# P1.net
KiCad netlist of a schematic drawn in Altium Designer
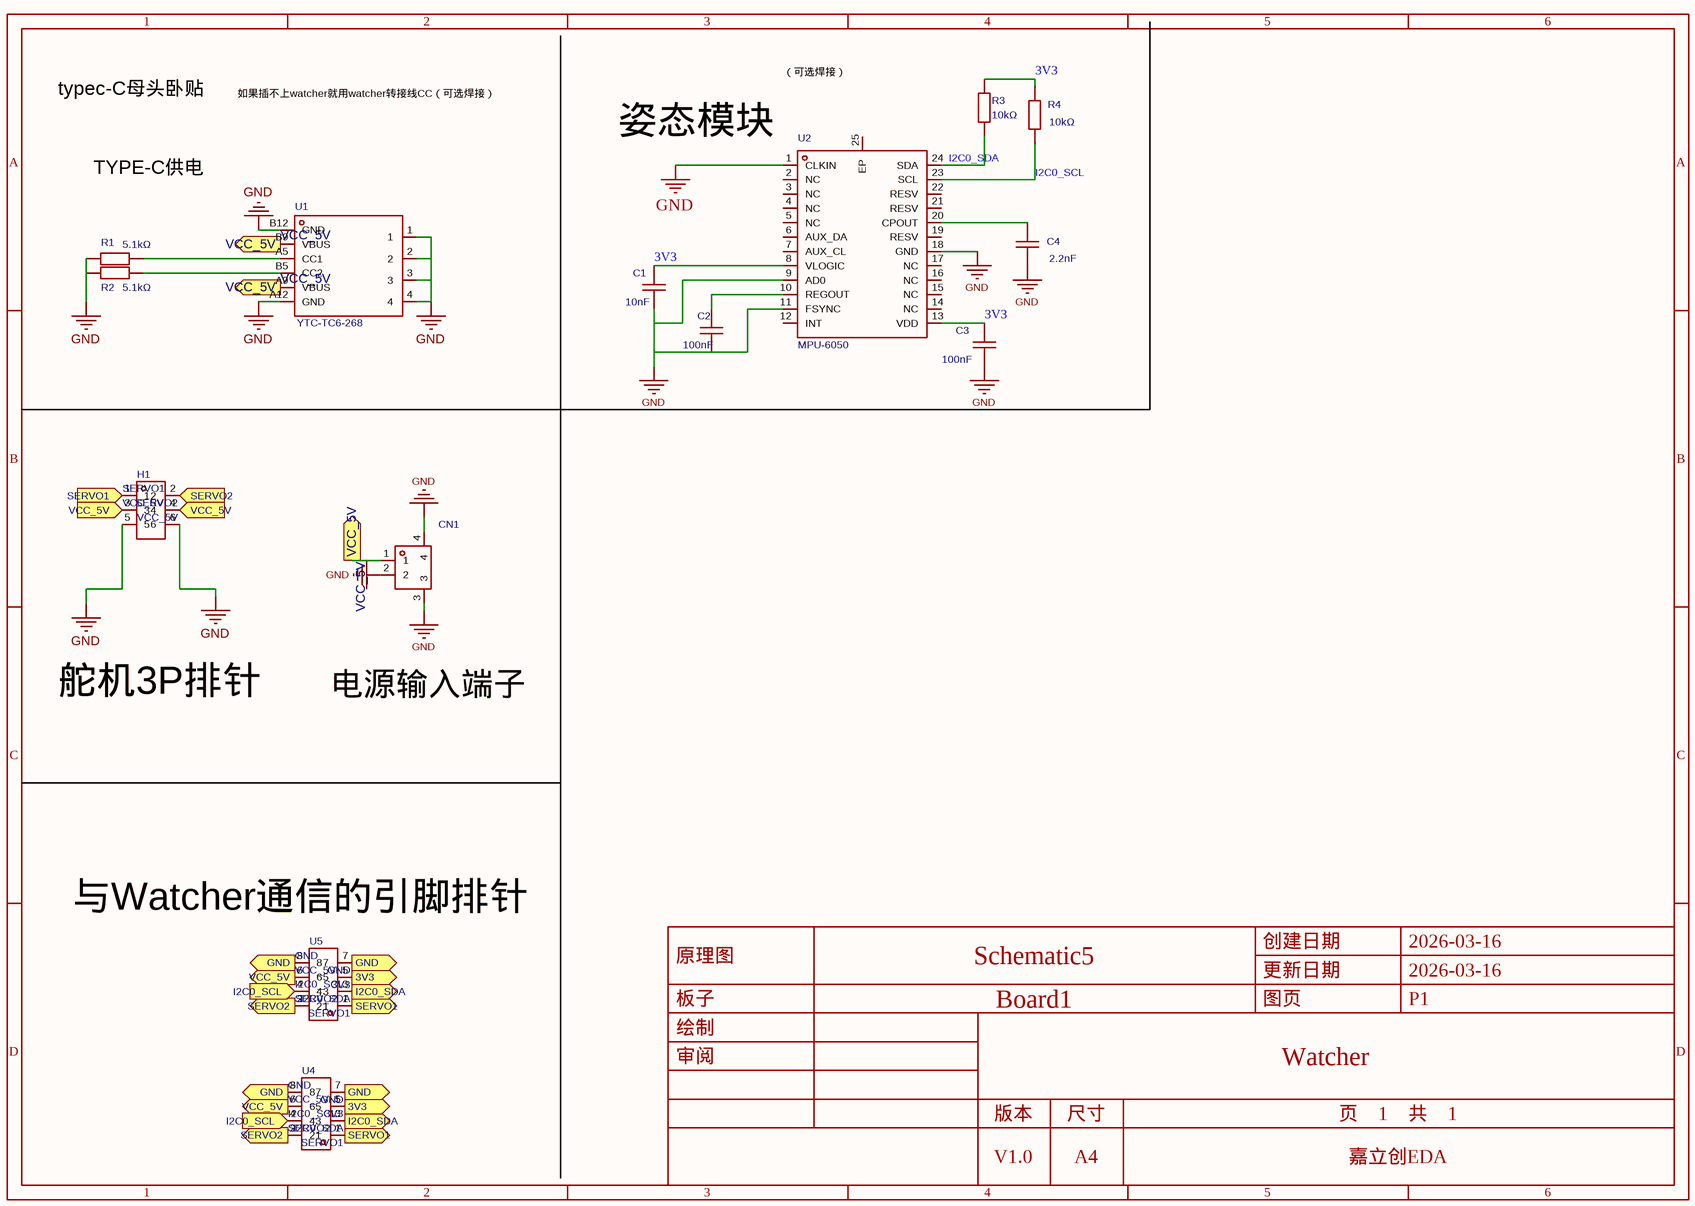
[diagram p0: P1.schdoc]

(export (version "E")
  (design (tool "Eeschema 10.0.6"))
  (components
    (comp (ref "C1")
      (value "10nF")
      (footprint "C0603")
      (description "容值:10nF;精度:±10%;额定电压:50V;材质(温度系数):X7R;")
      (fields (field (name "TOLERANCE") "±10%") (field (name "MANUFACTURER") "YAGEO(国巨)"))
      (libsource (lib "altium-import") (part "root_1_CC0603KRX7R9BB103_"))
    )
    (comp (ref "C2")
      (value "100nF")
      (footprint "C0603")
      (description "容值:100nF;精度:±10%;额定电压:50V;材质(温度系数):X7R;")
      (fields (field (name "TOLERANCE") "±10%") (field (name "MANUFACTURER") "FH(风华)"))
      (libsource (lib "altium-import") (part "root_1_0603B104K500NT_"))
    )
    (comp (ref "C3")
      (value "100nF")
      (footprint "C0603")
      (description "容值:100nF;精度:±10%;额定电压:50V;材质(温度系数):X7R;")
      (fields (field (name "TOLERANCE") "±10%") (field (name "MANUFACTURER") "FH(风华)"))
      (libsource (lib "altium-import") (part "root_1_0603B104K500NT_"))
    )
    (comp (ref "C4")
      (value "2.2nF")
      (footprint "C0603")
      (description "容值:2.2nF;精度:±10%;额定电压:50V;材质(温度系数):X7R;")
      (fields (field (name "MANUFACTURER") "FH(风华)") (field (name "MANUFACTURER PART") "0603B222K500NT"))
      (libsource (lib "altium-import") (part "root_1_0603B222K500NT_"))
    )
    (comp (ref "CN1")
      (value "SH1.0mm立式")
      (footprint "CONN-SMD_2P-P1.00_HC-1.0-2PLT")
      (libsource (lib "altium-import") (part "root_0_SH1.0mm立式_"))
    )
    (comp (ref "H1")
      (value "PZ254V-12-6P")
      (footprint "HDR-TH_6P-P2.54-V-M-R2-C3-S2.54")
      (fields (field (name "MANUFACTURER") "XFCN(兴飞)"))
      (libsource (lib "altium-import") (part "root_0_PZ254V-12-6P_"))
    )
    (comp (ref "R1")
      (value "5.1kΩ")
      (footprint "R0603_1")
      (description "电阻类型:厚膜电阻;阻值:5.1kΩ;精度:±1%;功率:100mW;温度系数:±100ppm/;最大工作电压:75V;工作温度范围:-55~+155;")
      (fields
        (field (name "MANUFACTURER") "UNI-ROYAL(厚声)")
        (field (name "MANUFACTURER PART") "0603WAF5101T5E")
      )
      (libsource (lib "altium-import") (part "root_0_0603WAF5101T5E_"))
    )
    (comp (ref "R2")
      (value "5.1kΩ")
      (footprint "R0603_1")
      (description "电阻类型:厚膜电阻;阻值:5.1kΩ;精度:±1%;功率:100mW;温度系数:±100ppm/;最大工作电压:75V;工作温度范围:-55~+155;")
      (fields
        (field (name "MANUFACTURER") "UNI-ROYAL(厚声)")
        (field (name "MANUFACTURER PART") "0603WAF5101T5E")
      )
      (libsource (lib "altium-import") (part "root_0_0603WAF5101T5E_"))
    )
    (comp (ref "R3")
      (value "10kΩ")
      (footprint "R0603")
      (description "电阻类型:厚膜电阻;阻值:10kΩ;精度:±1%;功率:100mW;最大工作电压:75V;温度系数:±100ppm/℃;")
      (fields (field (name "MANUFACTURER") "YAGEO(国巨)") (field (name "MANUFACTURER PART") "RC0603FR-0710KL"))
      (libsource (lib "altium-import") (part "root_1_RC0603FR-0710KL_"))
    )
    (comp (ref "R4")
      (value "10kΩ")
      (footprint "R0603")
      (description "电阻类型:厚膜电阻;阻值:10kΩ;精度:±1%;功率:100mW;最大工作电压:75V;温度系数:±100ppm/℃;")
      (fields (field (name "MANUFACTURER") "YAGEO(国巨)") (field (name "MANUFACTURER PART") "RC0603FR-0710KL"))
      (libsource (lib "altium-import") (part "root_1_RC0603FR-0710KL_"))
    )
    (comp (ref "U1")
      (value "YTC-TC6-268")
      (footprint "TYPE-C-SMD_YIYUAN_YTC-TC6-268")
      (description "连接器类型:Type-C;公母:母座;触点数量:6;")
      (fields (field (name "MANUFACTURER") "YIYUAN(怡远)"))
      (libsource (lib "altium-import") (part "root_0_YTC-TC6-268_"))
    )
    (comp (ref "U2")
      (value "MPU-6050")
      (footprint "QFN-24_L4.0-W4.0-P0.50-BL-EP2.7")
      (description "传感器类型:加速度计陀螺仪;")
      (fields (field (name "MANUFACTURER") "TDK InvenSense(应美盛)"))
      (libsource (lib "altium-import") (part "root_0_MPU-6050_"))
    )
    (comp (ref "U4")
      (value "PZ2.54-2*4")
      (footprint "HDR-TH_8P-P2.54-V-M-R2-C4-S2.54")
      (fields (field (name "MANUFACTURER") "ZHOURI(洲日)"))
      (libsource (lib "altium-import") (part "root_2_PZ2.54-2*4_"))
    )
    (comp (ref "U5")
      (value "PZ2.54-2*4")
      (footprint "HDR-TH_8P-P2.54-V-M-R2-C4-S2.54")
      (fields (field (name "MANUFACTURER") "ZHOURI(洲日)"))
      (libsource (lib "altium-import") (part "root_2_PZ2.54-2*4_"))
    )
  )
  (nets
    (net (code "1") (name "/3V3") (class "Default")
      (node (ref "C1") (pin "2") (pinfunction "2_2") (pintype "passive"))
      (node (ref "C3") (pin "2") (pinfunction "2_2") (pintype "passive"))
      (node (ref "R3") (pin "2") (pinfunction "2_2") (pintype "passive"))
      (node (ref "R4") (pin "2") (pinfunction "2_2") (pintype "passive"))
      (node (ref "U2") (pin "13") (pinfunction "VDD_13") (pintype "passive"))
      (node (ref "U2") (pin "8") (pinfunction "VLOGIC_8") (pintype "passive"))
      (node (ref "U4") (pin "5") (pinfunction "5_5") (pintype "passive"))
      (node (ref "U5") (pin "5") (pinfunction "5_5") (pintype "passive"))
    )
    (net (code "2") (name "/I2C0_SCL") (class "Default")
      (node (ref "R4") (pin "1") (pinfunction "1_1") (pintype "passive"))
      (node (ref "U2") (pin "23") (pinfunction "SCL_23") (pintype "passive"))
      (node (ref "U4") (pin "4") (pinfunction "4_4") (pintype "passive"))
      (node (ref "U5") (pin "4") (pinfunction "4_4") (pintype "passive"))
    )
    (net (code "3") (name "/I2C0_SDA") (class "Default")
      (node (ref "R3") (pin "1") (pinfunction "1_1") (pintype "passive"))
      (node (ref "U2") (pin "24") (pinfunction "SDA_24") (pintype "passive"))
      (node (ref "U4") (pin "3") (pinfunction "3_3") (pintype "passive"))
      (node (ref "U5") (pin "3") (pinfunction "3_3") (pintype "passive"))
    )
    (net (code "4") (name "/SERVO1") (class "Default")
      (node (ref "H1") (pin "1") (pinfunction "1_1") (pintype "passive"))
      (node (ref "U4") (pin "1") (pinfunction "1_1") (pintype "passive"))
      (node (ref "U5") (pin "1") (pinfunction "1_1") (pintype "passive"))
    )
    (net (code "5") (name "/SERVO2") (class "Default")
      (node (ref "H1") (pin "2") (pinfunction "2_2") (pintype "passive"))
      (node (ref "U4") (pin "2") (pinfunction "2_2") (pintype "passive"))
      (node (ref "U5") (pin "2") (pinfunction "2_2") (pintype "passive"))
    )
    (net (code "6") (name "/VCC_5V") (class "Default")
      (node (ref "CN1") (pin "1") (pinfunction "1_1") (pintype "passive"))
      (node (ref "H1") (pin "3") (pinfunction "3_3") (pintype "passive"))
      (node (ref "H1") (pin "4") (pinfunction "4_4") (pintype "passive"))
      (node (ref "U1") (pin "A9") (pinfunction "VBUS_A9") (pintype "passive"))
      (node (ref "U1") (pin "B9") (pinfunction "VBUS_B9") (pintype "passive"))
      (node (ref "U4") (pin "6") (pinfunction "6_6") (pintype "passive"))
      (node (ref "U5") (pin "6") (pinfunction "6_6") (pintype "passive"))
    )
    (net (code "7") (name "GND") (class "Default")
      (node (ref "C1") (pin "1") (pinfunction "1_1") (pintype "passive"))
      (node (ref "C2") (pin "1") (pinfunction "1_1") (pintype "passive"))
      (node (ref "C3") (pin "1") (pinfunction "1_1") (pintype "passive"))
      (node (ref "C4") (pin "1") (pinfunction "1_1") (pintype "passive"))
      (node (ref "CN1") (pin "2") (pinfunction "2_2") (pintype "passive"))
      (node (ref "CN1") (pin "3") (pinfunction "3_3") (pintype "passive"))
      (node (ref "CN1") (pin "4") (pinfunction "4_4") (pintype "passive"))
      (node (ref "H1") (pin "5") (pinfunction "5_5") (pintype "passive"))
      (node (ref "H1") (pin "6") (pinfunction "6_6") (pintype "passive"))
      (node (ref "R1") (pin "1") (pinfunction "1_1") (pintype "passive"))
      (node (ref "R2") (pin "1") (pinfunction "1_1") (pintype "passive"))
      (node (ref "U1") (pin "1") (pinfunction "1_1") (pintype "passive"))
      (node (ref "U1") (pin "2") (pinfunction "2_2") (pintype "passive"))
      (node (ref "U1") (pin "3") (pinfunction "3_3") (pintype "passive"))
      (node (ref "U1") (pin "4") (pinfunction "4_4") (pintype "passive"))
      (node (ref "U1") (pin "A12") (pinfunction "GND_A12") (pintype "passive"))
      (node (ref "U1") (pin "B12") (pinfunction "GND_B12") (pintype "passive"))
      (node (ref "U2") (pin "1") (pinfunction "CLKIN_1") (pintype "passive"))
      (node (ref "U2") (pin "11") (pinfunction "FSYNC_11") (pintype "passive"))
      (node (ref "U2") (pin "18") (pinfunction "GND_18") (pintype "passive"))
      (node (ref "U2") (pin "9") (pinfunction "AD0_9") (pintype "passive"))
      (node (ref "U4") (pin "7") (pinfunction "7_7") (pintype "passive"))
      (node (ref "U4") (pin "8") (pinfunction "8_8") (pintype "passive"))
      (node (ref "U5") (pin "7") (pinfunction "7_7") (pintype "passive"))
      (node (ref "U5") (pin "8") (pinfunction "8_8") (pintype "passive"))
    )
    (net (code "8") (name "Net-(U1-CC1)") (class "Default")
      (node (ref "R1") (pin "2") (pinfunction "2_2") (pintype "passive"))
      (node (ref "U1") (pin "A5") (pinfunction "CC1_A5") (pintype "passive"))
    )
    (net (code "9") (name "Net-(U1-CC2)") (class "Default")
      (node (ref "R2") (pin "2") (pinfunction "2_2") (pintype "passive"))
      (node (ref "U1") (pin "B5") (pinfunction "CC2_B5") (pintype "passive"))
    )
    (net (code "10") (name "Net-(U2-CPOUT)") (class "Default")
      (node (ref "C4") (pin "2") (pinfunction "2_2") (pintype "passive"))
      (node (ref "U2") (pin "20") (pinfunction "CPOUT_20") (pintype "passive"))
    )
    (net (code "11") (name "Net-(U2-REGOUT)") (class "Default")
      (node (ref "C2") (pin "2") (pinfunction "2_2") (pintype "passive"))
      (node (ref "U2") (pin "10") (pinfunction "REGOUT_10") (pintype "passive"))
    )
    (net (code "12") (name "unconnected-(U2-AUX_CL-Pad7)") (class "Default")
      (node (ref "U2") (pin "7") (pinfunction "AUX_CL_7") (pintype "passive"))
    )
    (net (code "13") (name "unconnected-(U2-AUX_DA-Pad6)") (class "Default")
      (node (ref "U2") (pin "6") (pinfunction "AUX_DA_6") (pintype "passive"))
    )
    (net (code "14") (name "unconnected-(U2-EP-Pad25)") (class "Default")
      (node (ref "U2") (pin "25") (pinfunction "EP_25") (pintype "passive"))
    )
    (net (code "15") (name "unconnected-(U2-INT-Pad12)") (class "Default")
      (node (ref "U2") (pin "12") (pinfunction "INT_12") (pintype "passive"))
    )
    (net (code "16") (name "unconnected-(U2-NC-Pad2)") (class "Default")
      (node (ref "U2") (pin "2") (pinfunction "NC_2") (pintype "passive"))
    )
    (net (code "17") (name "unconnected-(U2-NC-Pad3)") (class "Default")
      (node (ref "U2") (pin "3") (pinfunction "NC_3") (pintype "passive"))
    )
    (net (code "18") (name "unconnected-(U2-NC-Pad4)") (class "Default")
      (node (ref "U2") (pin "4") (pinfunction "NC_4") (pintype "passive"))
    )
    (net (code "19") (name "unconnected-(U2-NC-Pad5)") (class "Default")
      (node (ref "U2") (pin "5") (pinfunction "NC_5") (pintype "passive"))
    )
    (net (code "20") (name "unconnected-(U2-NC-Pad14)") (class "Default")
      (node (ref "U2") (pin "14") (pinfunction "NC_14") (pintype "passive"))
    )
    (net (code "21") (name "unconnected-(U2-NC-Pad15)") (class "Default")
      (node (ref "U2") (pin "15") (pinfunction "NC_15") (pintype "passive"))
    )
    (net (code "22") (name "unconnected-(U2-NC-Pad16)") (class "Default")
      (node (ref "U2") (pin "16") (pinfunction "NC_16") (pintype "passive"))
    )
    (net (code "23") (name "unconnected-(U2-NC-Pad17)") (class "Default")
      (node (ref "U2") (pin "17") (pinfunction "NC_17") (pintype "passive"))
    )
    (net (code "24") (name "unconnected-(U2-RESV-Pad19)") (class "Default")
      (node (ref "U2") (pin "19") (pinfunction "RESV_19") (pintype "passive"))
    )
    (net (code "25") (name "unconnected-(U2-RESV-Pad21)") (class "Default")
      (node (ref "U2") (pin "21") (pinfunction "RESV_21") (pintype "passive"))
    )
    (net (code "26") (name "unconnected-(U2-RESV-Pad22)") (class "Default")
      (node (ref "U2") (pin "22") (pinfunction "RESV_22") (pintype "passive"))
    )
  )
)
